# M783bad.net
KiCad netlist of a schematic drawn in EAGLE
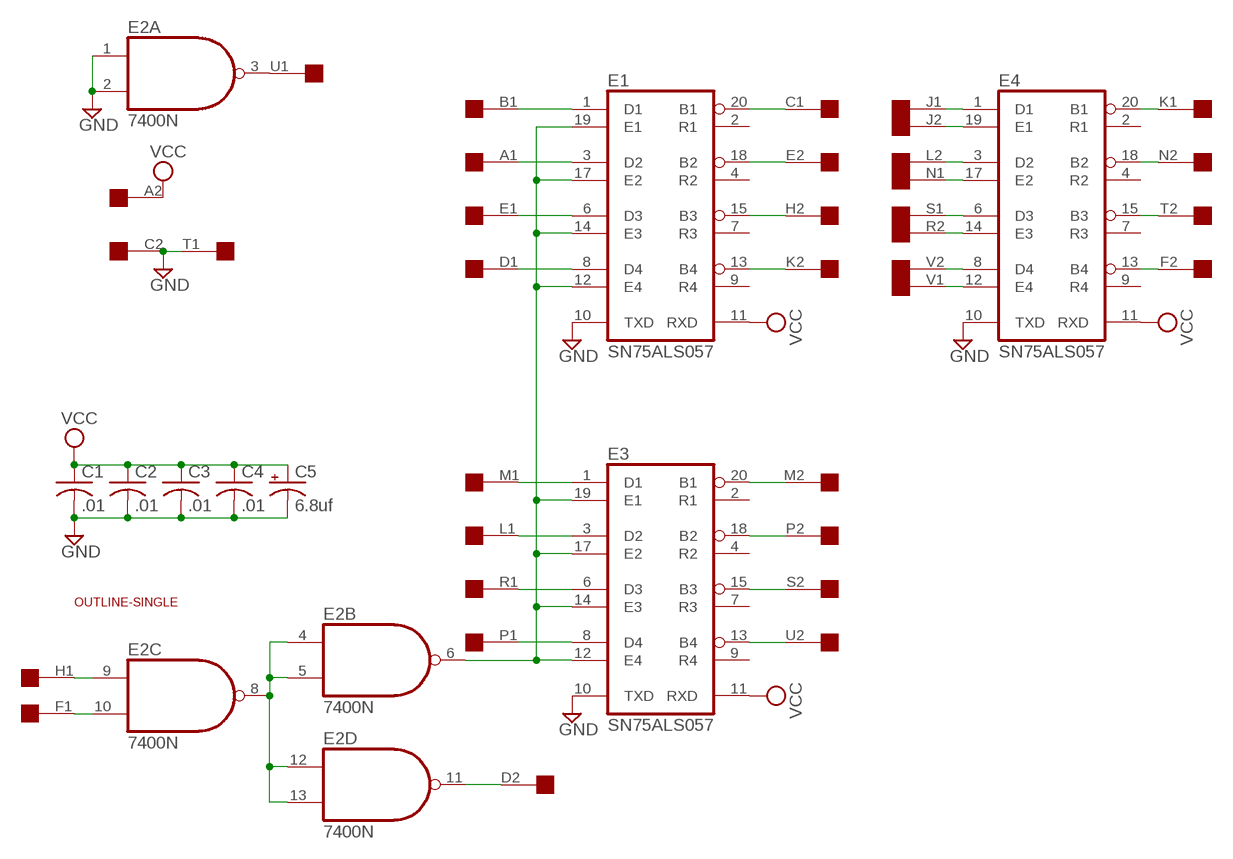
[diagram p0: schematic, sheet 1]

(export (version "E")
  (design (tool "Eeschema 10.0.6"))
  (components
    (comp (ref "C1")
      (value ".01")
      (footprint "eagle-import:C050-025X075")
      (libsource (lib "eagle-import") (part "C-US050-025X075"))
    )
    (comp (ref "C2")
      (value ".01")
      (footprint "eagle-import:C050-025X075")
      (libsource (lib "eagle-import") (part "C-US050-025X075"))
    )
    (comp (ref "C3")
      (value ".01")
      (footprint "eagle-import:C050-025X075")
      (libsource (lib "eagle-import") (part "C-US050-025X075"))
    )
    (comp (ref "C4")
      (value ".01")
      (footprint "eagle-import:C050-025X075")
      (libsource (lib "eagle-import") (part "C-US050-025X075"))
    )
    (comp (ref "C5")
      (value "6.8uf")
      (footprint "eagle-import:E15-5")
      (libsource (lib "eagle-import") (part "CPOL-USE15-5AXIAL"))
    )
    (comp (ref "E1")
      (value "SN75ALS057")
      (footprint "eagle-import:DIL20")
      (libsource (lib "eagle-import") (part "SN75ALS057"))
    )
    (comp (ref "E2")
      (value "7400N")
      (footprint "eagle-import:DIL14")
      (libsource (lib "eagle-import") (part "7400N"))
    )
    (comp (ref "E3")
      (value "SN75ALS057")
      (footprint "eagle-import:DIL20")
      (libsource (lib "eagle-import") (part "SN75ALS057"))
    )
    (comp (ref "E4")
      (value "SN75ALS057")
      (footprint "eagle-import:DIL20")
      (libsource (lib "eagle-import") (part "SN75ALS057"))
    )
    (comp (ref "U$1")
      (value "SINGLE")
      (footprint "eagle-import:EDGE-CON2")
      (libsource (lib "eagle-import") (part "SINGLE"))
    )
    (comp (ref "U$2")
      (value "OUTLINE-SINGLE")
      (footprint "eagle-import:SINGLE")
      (libsource (lib "eagle-import") (part "OUTLINE-SINGLE"))
    )
  )
  (nets
    (net (code "1") (name "GND") (class "Default")
      (node (ref "C1") (pin "2") (pinfunction "2_2") (pintype "passive"))
      (node (ref "C2") (pin "2") (pinfunction "2_2") (pintype "passive"))
      (node (ref "C3") (pin "2") (pinfunction "2_2") (pintype "passive"))
      (node (ref "C4") (pin "2") (pinfunction "2_2") (pintype "passive"))
      (node (ref "C5") (pin "-") (pinfunction "-_-") (pintype "passive"))
      (node (ref "E1") (pin "10") (pinfunction "TXD_10") (pintype "input"))
      (node (ref "E2") (pin "1") (pinfunction "I0_1") (pintype "input"))
      (node (ref "E2") (pin "2") (pinfunction "I1_2") (pintype "input"))
      (node (ref "E3") (pin "10") (pinfunction "TXD_10") (pintype "input"))
      (node (ref "E4") (pin "10") (pinfunction "TXD_10") (pintype "input"))
      (node (ref "U$1") (pin "C2") (pinfunction "1_C2") (pintype "bidirectional"))
      (node (ref "U$1") (pin "T1") (pinfunction "1_T1") (pintype "bidirectional"))
    )
    (net (code "2") (name "Net-(E1A-B1)") (class "Default")
      (node (ref "E1") (pin "20") (pinfunction "B1_20") (pintype "bidirectional"))
      (node (ref "U$1") (pin "C1") (pinfunction "1_C1") (pintype "bidirectional"))
    )
    (net (code "3") (name "Net-(E1A-B2)") (class "Default")
      (node (ref "E1") (pin "18") (pinfunction "B2_18") (pintype "bidirectional"))
      (node (ref "U$1") (pin "E2") (pinfunction "1_E2") (pintype "bidirectional"))
    )
    (net (code "4") (name "Net-(E1A-B3)") (class "Default")
      (node (ref "E1") (pin "15") (pinfunction "B3_15") (pintype "bidirectional"))
      (node (ref "U$1") (pin "H2") (pinfunction "1_H2") (pintype "bidirectional"))
    )
    (net (code "5") (name "Net-(E1A-B4)") (class "Default")
      (node (ref "E1") (pin "13") (pinfunction "B4_13") (pintype "bidirectional"))
      (node (ref "U$1") (pin "K2") (pinfunction "1_K2") (pintype "bidirectional"))
    )
    (net (code "6") (name "Net-(E1A-D1)") (class "Default")
      (node (ref "E1") (pin "1") (pinfunction "D1_1") (pintype "input"))
      (node (ref "U$1") (pin "B1") (pinfunction "1_B1") (pintype "bidirectional"))
    )
    (net (code "7") (name "Net-(E1A-D2)") (class "Default")
      (node (ref "E1") (pin "3") (pinfunction "D2_3") (pintype "input"))
      (node (ref "U$1") (pin "A1") (pinfunction "1_A1") (pintype "bidirectional"))
    )
    (net (code "8") (name "Net-(E1A-D3)") (class "Default")
      (node (ref "E1") (pin "6") (pinfunction "D3_6") (pintype "input"))
      (node (ref "U$1") (pin "E1") (pinfunction "1_E1") (pintype "bidirectional"))
    )
    (net (code "9") (name "Net-(E1A-D4)") (class "Default")
      (node (ref "E1") (pin "8") (pinfunction "D4_8") (pintype "input"))
      (node (ref "U$1") (pin "D1") (pinfunction "1_D1") (pintype "bidirectional"))
    )
    (net (code "10") (name "Net-(E1A-E1)") (class "Default")
      (node (ref "E1") (pin "12") (pinfunction "E4_12") (pintype "input"))
      (node (ref "E1") (pin "14") (pinfunction "E3_14") (pintype "input"))
      (node (ref "E1") (pin "17") (pinfunction "E2_17") (pintype "input"))
      (node (ref "E1") (pin "19") (pinfunction "E1_19") (pintype "input"))
      (node (ref "E2") (pin "6") (pinfunction "O_6") (pintype "output"))
      (node (ref "E3") (pin "12") (pinfunction "E4_12") (pintype "input"))
      (node (ref "E3") (pin "14") (pinfunction "E3_14") (pintype "input"))
      (node (ref "E3") (pin "17") (pinfunction "E2_17") (pintype "input"))
      (node (ref "E3") (pin "19") (pinfunction "E1_19") (pintype "input"))
    )
    (net (code "11") (name "Net-(E2A-O)") (class "Default")
      (node (ref "E2") (pin "3") (pinfunction "O_3") (pintype "output"))
      (node (ref "U$1") (pin "U1") (pinfunction "1_U1") (pintype "bidirectional"))
    )
    (net (code "12") (name "Net-(E2B-I0)") (class "Default")
      (node (ref "E2") (pin "12") (pinfunction "I0_12") (pintype "input"))
      (node (ref "E2") (pin "13") (pinfunction "I1_13") (pintype "input"))
      (node (ref "E2") (pin "4") (pinfunction "I0_4") (pintype "input"))
      (node (ref "E2") (pin "5") (pinfunction "I1_5") (pintype "input"))
      (node (ref "E2") (pin "8") (pinfunction "O_8") (pintype "output"))
    )
    (net (code "13") (name "Net-(E2C-I0)") (class "Default")
      (node (ref "E2") (pin "9") (pinfunction "I0_9") (pintype "input"))
      (node (ref "U$1") (pin "H1") (pinfunction "1_H1") (pintype "bidirectional"))
    )
    (net (code "14") (name "Net-(E2C-I1)") (class "Default")
      (node (ref "E2") (pin "10") (pinfunction "I1_10") (pintype "input"))
      (node (ref "U$1") (pin "F1") (pinfunction "1_F1") (pintype "bidirectional"))
    )
    (net (code "15") (name "Net-(E2D-O)") (class "Default")
      (node (ref "E2") (pin "11") (pinfunction "O_11") (pintype "output"))
      (node (ref "U$1") (pin "D2") (pinfunction "1_D2") (pintype "bidirectional"))
    )
    (net (code "16") (name "Net-(E3A-B1)") (class "Default")
      (node (ref "E3") (pin "20") (pinfunction "B1_20") (pintype "bidirectional"))
      (node (ref "U$1") (pin "M2") (pinfunction "1_M2") (pintype "bidirectional"))
    )
    (net (code "17") (name "Net-(E3A-B2)") (class "Default")
      (node (ref "E3") (pin "18") (pinfunction "B2_18") (pintype "bidirectional"))
      (node (ref "U$1") (pin "P2") (pinfunction "1_P2") (pintype "bidirectional"))
    )
    (net (code "18") (name "Net-(E3A-B3)") (class "Default")
      (node (ref "E3") (pin "15") (pinfunction "B3_15") (pintype "bidirectional"))
      (node (ref "U$1") (pin "S2") (pinfunction "1_S2") (pintype "bidirectional"))
    )
    (net (code "19") (name "Net-(E3A-B4)") (class "Default")
      (node (ref "E3") (pin "13") (pinfunction "B4_13") (pintype "bidirectional"))
      (node (ref "U$1") (pin "U2") (pinfunction "1_U2") (pintype "bidirectional"))
    )
    (net (code "20") (name "Net-(E3A-D1)") (class "Default")
      (node (ref "E3") (pin "1") (pinfunction "D1_1") (pintype "input"))
      (node (ref "U$1") (pin "M1") (pinfunction "1_M1") (pintype "bidirectional"))
    )
    (net (code "21") (name "Net-(E3A-D2)") (class "Default")
      (node (ref "E3") (pin "3") (pinfunction "D2_3") (pintype "input"))
      (node (ref "U$1") (pin "L1") (pinfunction "1_L1") (pintype "bidirectional"))
    )
    (net (code "22") (name "Net-(E3A-D3)") (class "Default")
      (node (ref "E3") (pin "6") (pinfunction "D3_6") (pintype "input"))
      (node (ref "U$1") (pin "R1") (pinfunction "1_R1") (pintype "bidirectional"))
    )
    (net (code "23") (name "Net-(E3A-D4)") (class "Default")
      (node (ref "E3") (pin "8") (pinfunction "D4_8") (pintype "input"))
      (node (ref "U$1") (pin "P1") (pinfunction "1_P1") (pintype "bidirectional"))
    )
    (net (code "24") (name "Net-(E4A-B1)") (class "Default")
      (node (ref "E4") (pin "20") (pinfunction "B1_20") (pintype "bidirectional"))
      (node (ref "U$1") (pin "K1") (pinfunction "1_K1") (pintype "bidirectional"))
    )
    (net (code "25") (name "Net-(E4A-B2)") (class "Default")
      (node (ref "E4") (pin "18") (pinfunction "B2_18") (pintype "bidirectional"))
      (node (ref "U$1") (pin "N2") (pinfunction "1_N2") (pintype "bidirectional"))
    )
    (net (code "26") (name "Net-(E4A-B3)") (class "Default")
      (node (ref "E4") (pin "15") (pinfunction "B3_15") (pintype "bidirectional"))
      (node (ref "U$1") (pin "T2") (pinfunction "1_T2") (pintype "bidirectional"))
    )
    (net (code "27") (name "Net-(E4A-B4)") (class "Default")
      (node (ref "E4") (pin "13") (pinfunction "B4_13") (pintype "bidirectional"))
      (node (ref "U$1") (pin "F2") (pinfunction "1_F2") (pintype "bidirectional"))
    )
    (net (code "28") (name "Net-(E4A-D1)") (class "Default")
      (node (ref "E4") (pin "1") (pinfunction "D1_1") (pintype "input"))
      (node (ref "U$1") (pin "J1") (pinfunction "1_J1") (pintype "bidirectional"))
    )
    (net (code "29") (name "Net-(E4A-D2)") (class "Default")
      (node (ref "E4") (pin "3") (pinfunction "D2_3") (pintype "input"))
      (node (ref "U$1") (pin "L2") (pinfunction "1_L2") (pintype "bidirectional"))
    )
    (net (code "30") (name "Net-(E4A-D3)") (class "Default")
      (node (ref "E4") (pin "6") (pinfunction "D3_6") (pintype "input"))
      (node (ref "U$1") (pin "S1") (pinfunction "1_S1") (pintype "bidirectional"))
    )
    (net (code "31") (name "Net-(E4A-D4)") (class "Default")
      (node (ref "E4") (pin "8") (pinfunction "D4_8") (pintype "input"))
      (node (ref "U$1") (pin "V2") (pinfunction "1_V2") (pintype "bidirectional"))
    )
    (net (code "32") (name "Net-(E4A-E1)") (class "Default")
      (node (ref "E4") (pin "19") (pinfunction "E1_19") (pintype "input"))
      (node (ref "U$1") (pin "J2") (pinfunction "1_J2") (pintype "bidirectional"))
    )
    (net (code "33") (name "Net-(E4A-E2)") (class "Default")
      (node (ref "E4") (pin "17") (pinfunction "E2_17") (pintype "input"))
      (node (ref "U$1") (pin "N1") (pinfunction "1_N1") (pintype "bidirectional"))
    )
    (net (code "34") (name "Net-(E4A-E3)") (class "Default")
      (node (ref "E4") (pin "14") (pinfunction "E3_14") (pintype "input"))
      (node (ref "U$1") (pin "R2") (pinfunction "1_R2") (pintype "bidirectional"))
    )
    (net (code "35") (name "Net-(E4A-E4)") (class "Default")
      (node (ref "E4") (pin "12") (pinfunction "E4_12") (pintype "input"))
      (node (ref "U$1") (pin "V1") (pinfunction "1_V1") (pintype "bidirectional"))
    )
    (net (code "36") (name "VCC") (class "Default")
      (node (ref "C1") (pin "1") (pinfunction "1_1") (pintype "passive"))
      (node (ref "C2") (pin "1") (pinfunction "1_1") (pintype "passive"))
      (node (ref "C3") (pin "1") (pinfunction "1_1") (pintype "passive"))
      (node (ref "C4") (pin "1") (pinfunction "1_1") (pintype "passive"))
      (node (ref "C5") (pin "+") (pinfunction "+_+") (pintype "passive"))
      (node (ref "E1") (pin "11") (pinfunction "RXD_11") (pintype "input"))
      (node (ref "E3") (pin "11") (pinfunction "RXD_11") (pintype "input"))
      (node (ref "E4") (pin "11") (pinfunction "RXD_11") (pintype "input"))
      (node (ref "U$1") (pin "A2") (pinfunction "1_A2") (pintype "bidirectional"))
    )
    (net (code "37") (name "unconnected-(E1A-R1-Pad2)") (class "Default")
      (node (ref "E1") (pin "2") (pinfunction "R1_2") (pintype "output"))
    )
    (net (code "38") (name "unconnected-(E1A-R2-Pad4)") (class "Default")
      (node (ref "E1") (pin "4") (pinfunction "R2_4") (pintype "output"))
    )
    (net (code "39") (name "unconnected-(E1A-R3-Pad7)") (class "Default")
      (node (ref "E1") (pin "7") (pinfunction "R3_7") (pintype "output"))
    )
    (net (code "40") (name "unconnected-(E1A-R4-Pad9)") (class "Default")
      (node (ref "E1") (pin "9") (pinfunction "R4_9") (pintype "output"))
    )
    (net (code "41") (name "unconnected-(E3A-R1-Pad2)") (class "Default")
      (node (ref "E3") (pin "2") (pinfunction "R1_2") (pintype "output"))
    )
    (net (code "42") (name "unconnected-(E3A-R2-Pad4)") (class "Default")
      (node (ref "E3") (pin "4") (pinfunction "R2_4") (pintype "output"))
    )
    (net (code "43") (name "unconnected-(E3A-R3-Pad7)") (class "Default")
      (node (ref "E3") (pin "7") (pinfunction "R3_7") (pintype "output"))
    )
    (net (code "44") (name "unconnected-(E3A-R4-Pad9)") (class "Default")
      (node (ref "E3") (pin "9") (pinfunction "R4_9") (pintype "output"))
    )
    (net (code "45") (name "unconnected-(E4A-R1-Pad2)") (class "Default")
      (node (ref "E4") (pin "2") (pinfunction "R1_2") (pintype "output"))
    )
    (net (code "46") (name "unconnected-(E4A-R2-Pad4)") (class "Default")
      (node (ref "E4") (pin "4") (pinfunction "R2_4") (pintype "output"))
    )
    (net (code "47") (name "unconnected-(E4A-R3-Pad7)") (class "Default")
      (node (ref "E4") (pin "7") (pinfunction "R3_7") (pintype "output"))
    )
    (net (code "48") (name "unconnected-(E4A-R4-Pad9)") (class "Default")
      (node (ref "E4") (pin "9") (pinfunction "R4_9") (pintype "output"))
    )
  )
)
